# gatorstepper.net
KiCad netlist of a schematic drawn in EAGLE
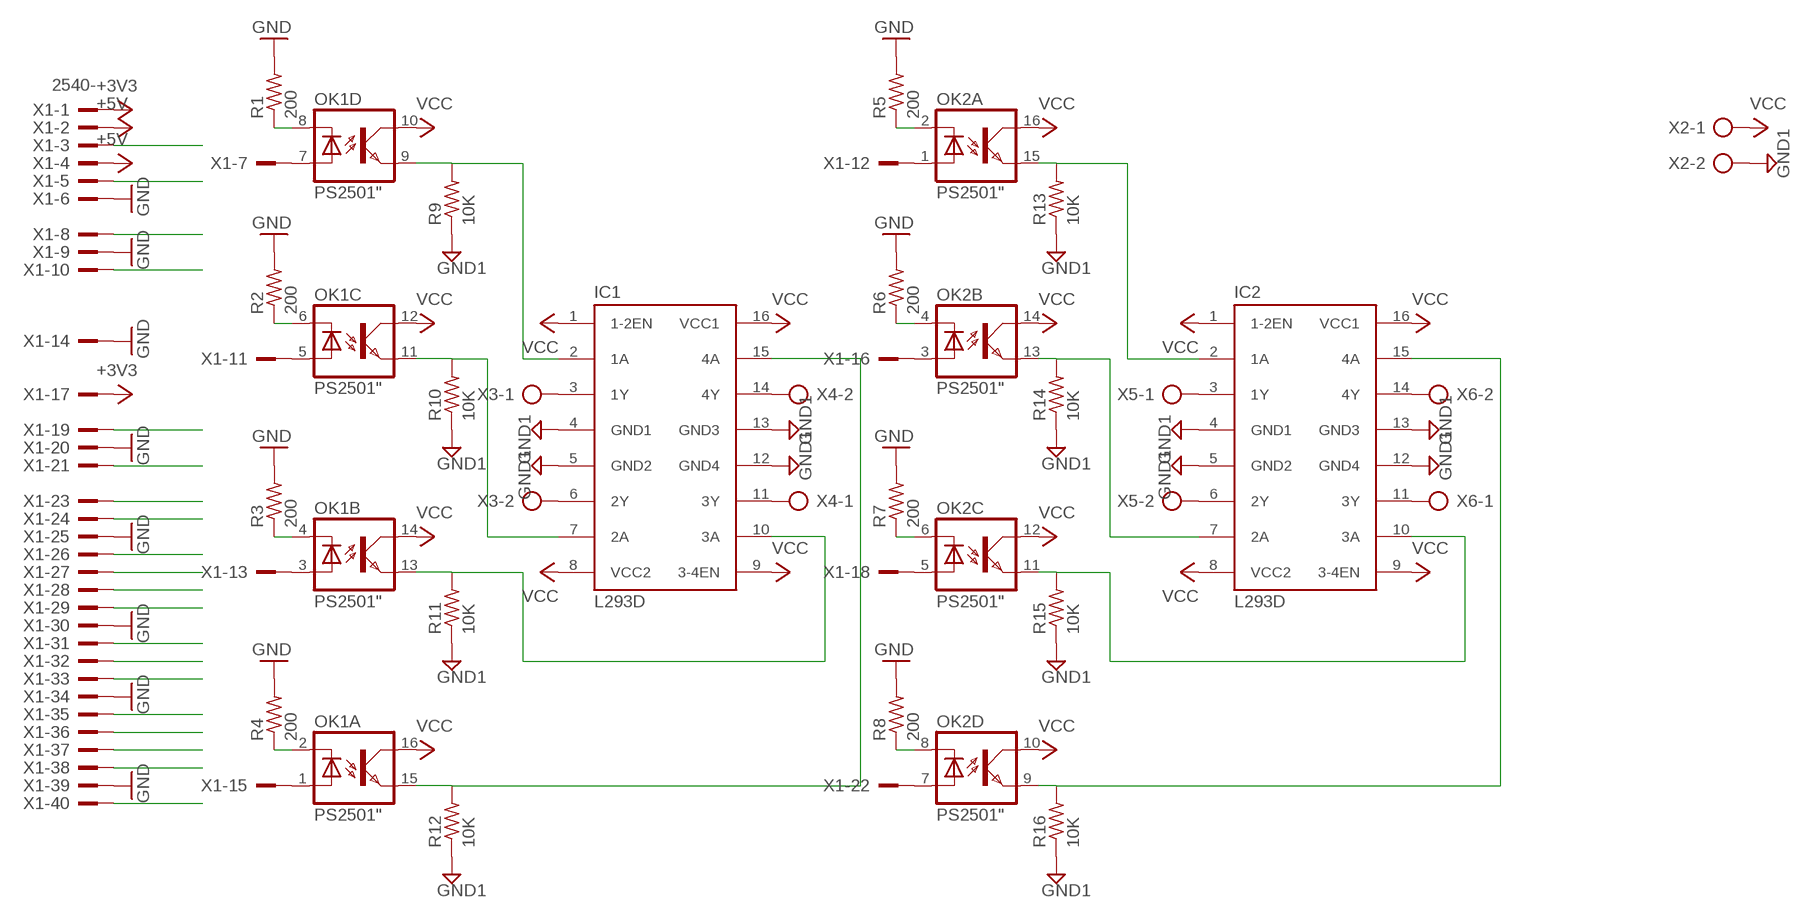
[diagram p0: schematic, sheet 1]

(export (version "E")
  (design (tool "Eeschema 10.0.6"))
  (components
    (comp (ref "IC1")
      (value "L293D")
      (footprint "eagle-import:DIL16")
      (libsource (lib "eagle-import") (part "L293D"))
    )
    (comp (ref "IC2")
      (value "L293D")
      (footprint "eagle-import:DIL16")
      (libsource (lib "eagle-import") (part "L293D"))
    )
    (comp (ref "OK1")
      (value "PS2501\"")
      (footprint "eagle-import:DIL16")
      (libsource (lib "eagle-import") (part "PS2501{dblquote}"))
    )
    (comp (ref "OK2")
      (value "PS2501\"")
      (footprint "eagle-import:DIL16")
      (libsource (lib "eagle-import") (part "PS2501{dblquote}"))
    )
    (comp (ref "R1")
      (value "200")
      (footprint "eagle-import:0207_12")
      (libsource (lib "eagle-import") (part "R-US_0207/12"))
    )
    (comp (ref "R2")
      (value "200")
      (footprint "eagle-import:0207_12")
      (libsource (lib "eagle-import") (part "R-US_0207/12"))
    )
    (comp (ref "R3")
      (value "200")
      (footprint "eagle-import:0207_12")
      (libsource (lib "eagle-import") (part "R-US_0207/12"))
    )
    (comp (ref "R4")
      (value "200")
      (footprint "eagle-import:0207_12")
      (libsource (lib "eagle-import") (part "R-US_0207/12"))
    )
    (comp (ref "R5")
      (value "200")
      (footprint "eagle-import:0207_12")
      (libsource (lib "eagle-import") (part "R-US_0207/12"))
    )
    (comp (ref "R6")
      (value "200")
      (footprint "eagle-import:0207_12")
      (libsource (lib "eagle-import") (part "R-US_0207/12"))
    )
    (comp (ref "R7")
      (value "200")
      (footprint "eagle-import:0207_12")
      (libsource (lib "eagle-import") (part "R-US_0207/12"))
    )
    (comp (ref "R8")
      (value "200")
      (footprint "eagle-import:0207_12")
      (libsource (lib "eagle-import") (part "R-US_0207/12"))
    )
    (comp (ref "R9")
      (value "10K")
      (footprint "eagle-import:0207_12")
      (libsource (lib "eagle-import") (part "R-US_0207/12"))
    )
    (comp (ref "R10")
      (value "10K")
      (footprint "eagle-import:0207_12")
      (libsource (lib "eagle-import") (part "R-US_0207/12"))
    )
    (comp (ref "R11")
      (value "10K")
      (footprint "eagle-import:0207_12")
      (libsource (lib "eagle-import") (part "R-US_0207/12"))
    )
    (comp (ref "R12")
      (value "10K")
      (footprint "eagle-import:0207_12")
      (libsource (lib "eagle-import") (part "R-US_0207/12"))
    )
    (comp (ref "R13")
      (value "10K")
      (footprint "eagle-import:0207_12")
      (libsource (lib "eagle-import") (part "R-US_0207/12"))
    )
    (comp (ref "R14")
      (value "10K")
      (footprint "eagle-import:0207_12")
      (libsource (lib "eagle-import") (part "R-US_0207/12"))
    )
    (comp (ref "R15")
      (value "10K")
      (footprint "eagle-import:0207_12")
      (libsource (lib "eagle-import") (part "R-US_0207/12"))
    )
    (comp (ref "R16")
      (value "10K")
      (footprint "eagle-import:0207_12")
      (libsource (lib "eagle-import") (part "R-US_0207/12"))
    )
    (comp (ref "X1")
      (value "2540-")
      (footprint "eagle-import:PAK100_2500-40")
      (libsource (lib "eagle-import") (part "2540-"))
    )
    (comp (ref "X2")
      (value "AK300/2")
      (footprint "eagle-import:AK300_2")
      (libsource (lib "eagle-import") (part "AK300/2"))
    )
    (comp (ref "X3")
      (value "AK300/2")
      (footprint "eagle-import:AK300_2")
      (libsource (lib "eagle-import") (part "AK300/2"))
    )
    (comp (ref "X4")
      (value "AK300/2")
      (footprint "eagle-import:AK300_2")
      (libsource (lib "eagle-import") (part "AK300/2"))
    )
    (comp (ref "X5")
      (value "AK300/2")
      (footprint "eagle-import:AK300_2")
      (libsource (lib "eagle-import") (part "AK300/2"))
    )
    (comp (ref "X6")
      (value "AK300/2")
      (footprint "eagle-import:AK300_2")
      (libsource (lib "eagle-import") (part "AK300/2"))
    )
  )
  (nets
    (net (code "1") (name "+3V3") (class "Default")
      (node (ref "X1") (pin "1") (pinfunction "KL_1") (pintype "passive"))
      (node (ref "X1") (pin "17") (pinfunction "KL_17") (pintype "passive"))
    )
    (net (code "2") (name "+5V") (class "Default")
      (node (ref "X1") (pin "2") (pinfunction "KL_2") (pintype "passive"))
      (node (ref "X1") (pin "4") (pinfunction "KL_4") (pintype "passive"))
    )
    (net (code "3") (name "GND") (class "Default")
      (node (ref "R1") (pin "2") (pinfunction "2_2") (pintype "passive"))
      (node (ref "R2") (pin "2") (pinfunction "2_2") (pintype "passive"))
      (node (ref "R3") (pin "2") (pinfunction "2_2") (pintype "passive"))
      (node (ref "R4") (pin "2") (pinfunction "2_2") (pintype "passive"))
      (node (ref "R5") (pin "2") (pinfunction "2_2") (pintype "passive"))
      (node (ref "R6") (pin "2") (pinfunction "2_2") (pintype "passive"))
      (node (ref "R7") (pin "2") (pinfunction "2_2") (pintype "passive"))
      (node (ref "R8") (pin "2") (pinfunction "2_2") (pintype "passive"))
      (node (ref "X1") (pin "14") (pinfunction "KL_14") (pintype "passive"))
      (node (ref "X1") (pin "20") (pinfunction "KL_20") (pintype "passive"))
      (node (ref "X1") (pin "25") (pinfunction "KL_25") (pintype "passive"))
      (node (ref "X1") (pin "30") (pinfunction "KL_30") (pintype "passive"))
      (node (ref "X1") (pin "34") (pinfunction "KL_34") (pintype "passive"))
      (node (ref "X1") (pin "39") (pinfunction "KL_39") (pintype "passive"))
      (node (ref "X1") (pin "6") (pinfunction "KL_6") (pintype "passive"))
      (node (ref "X1") (pin "9") (pinfunction "KL_9") (pintype "passive"))
    )
    (net (code "4") (name "GND1") (class "Default")
      (node (ref "IC1") (pin "12") (pinfunction "GND4_12") (pintype "power_in"))
      (node (ref "IC1") (pin "13") (pinfunction "GND3_13") (pintype "power_in"))
      (node (ref "IC1") (pin "4") (pinfunction "GND1_4") (pintype "power_in"))
      (node (ref "IC1") (pin "5") (pinfunction "GND2_5") (pintype "power_in"))
      (node (ref "IC2") (pin "12") (pinfunction "GND4_12") (pintype "power_in"))
      (node (ref "IC2") (pin "13") (pinfunction "GND3_13") (pintype "power_in"))
      (node (ref "IC2") (pin "4") (pinfunction "GND1_4") (pintype "power_in"))
      (node (ref "IC2") (pin "5") (pinfunction "GND2_5") (pintype "power_in"))
      (node (ref "R10") (pin "1") (pinfunction "1_1") (pintype "passive"))
      (node (ref "R11") (pin "1") (pinfunction "1_1") (pintype "passive"))
      (node (ref "R12") (pin "1") (pinfunction "1_1") (pintype "passive"))
      (node (ref "R13") (pin "1") (pinfunction "1_1") (pintype "passive"))
      (node (ref "R14") (pin "1") (pinfunction "1_1") (pintype "passive"))
      (node (ref "R15") (pin "1") (pinfunction "1_1") (pintype "passive"))
      (node (ref "R16") (pin "1") (pinfunction "1_1") (pintype "passive"))
      (node (ref "R9") (pin "1") (pinfunction "1_1") (pintype "passive"))
      (node (ref "X2") (pin "2") (pinfunction "KL_2") (pintype "passive"))
    )
    (net (code "5") (name "Net-(IC1-1A)") (class "Default")
      (node (ref "IC1") (pin "2") (pinfunction "1A_2") (pintype "input"))
      (node (ref "OK1") (pin "9") (pinfunction "EMI_9") (pintype "passive"))
      (node (ref "R9") (pin "2") (pinfunction "2_2") (pintype "passive"))
    )
    (net (code "6") (name "Net-(IC1-1Y)") (class "Default")
      (node (ref "IC1") (pin "3") (pinfunction "1Y_3") (pintype "output"))
      (node (ref "X3") (pin "1") (pinfunction "KL_1") (pintype "passive"))
    )
    (net (code "7") (name "Net-(IC1-2A)") (class "Default")
      (node (ref "IC1") (pin "7") (pinfunction "2A_7") (pintype "input"))
      (node (ref "OK1") (pin "11") (pinfunction "EMI_11") (pintype "passive"))
      (node (ref "R10") (pin "2") (pinfunction "2_2") (pintype "passive"))
    )
    (net (code "8") (name "Net-(IC1-2Y)") (class "Default")
      (node (ref "IC1") (pin "6") (pinfunction "2Y_6") (pintype "output"))
      (node (ref "X3") (pin "2") (pinfunction "KL_2") (pintype "passive"))
    )
    (net (code "9") (name "Net-(IC1-3A)") (class "Default")
      (node (ref "IC1") (pin "10") (pinfunction "3A_10") (pintype "input"))
      (node (ref "OK1") (pin "13") (pinfunction "EMI_13") (pintype "passive"))
      (node (ref "R11") (pin "2") (pinfunction "2_2") (pintype "passive"))
    )
    (net (code "10") (name "Net-(IC1-3Y)") (class "Default")
      (node (ref "IC1") (pin "11") (pinfunction "3Y_11") (pintype "output"))
      (node (ref "X4") (pin "1") (pinfunction "KL_1") (pintype "passive"))
    )
    (net (code "11") (name "Net-(IC1-4A)") (class "Default")
      (node (ref "IC1") (pin "15") (pinfunction "4A_15") (pintype "input"))
      (node (ref "OK1") (pin "15") (pinfunction "EMI_15") (pintype "passive"))
      (node (ref "R12") (pin "2") (pinfunction "2_2") (pintype "passive"))
    )
    (net (code "12") (name "Net-(IC1-4Y)") (class "Default")
      (node (ref "IC1") (pin "14") (pinfunction "4Y_14") (pintype "output"))
      (node (ref "X4") (pin "2") (pinfunction "KL_2") (pintype "passive"))
    )
    (net (code "13") (name "Net-(IC2-1A)") (class "Default")
      (node (ref "IC2") (pin "2") (pinfunction "1A_2") (pintype "input"))
      (node (ref "OK2") (pin "15") (pinfunction "EMI_15") (pintype "passive"))
      (node (ref "R13") (pin "2") (pinfunction "2_2") (pintype "passive"))
    )
    (net (code "14") (name "Net-(IC2-1Y)") (class "Default")
      (node (ref "IC2") (pin "3") (pinfunction "1Y_3") (pintype "output"))
      (node (ref "X5") (pin "1") (pinfunction "KL_1") (pintype "passive"))
    )
    (net (code "15") (name "Net-(IC2-2A)") (class "Default")
      (node (ref "IC2") (pin "7") (pinfunction "2A_7") (pintype "input"))
      (node (ref "OK2") (pin "13") (pinfunction "EMI_13") (pintype "passive"))
      (node (ref "R14") (pin "2") (pinfunction "2_2") (pintype "passive"))
    )
    (net (code "16") (name "Net-(IC2-2Y)") (class "Default")
      (node (ref "IC2") (pin "6") (pinfunction "2Y_6") (pintype "output"))
      (node (ref "X5") (pin "2") (pinfunction "KL_2") (pintype "passive"))
    )
    (net (code "17") (name "Net-(IC2-3A)") (class "Default")
      (node (ref "IC2") (pin "10") (pinfunction "3A_10") (pintype "input"))
      (node (ref "OK2") (pin "11") (pinfunction "EMI_11") (pintype "passive"))
      (node (ref "R15") (pin "2") (pinfunction "2_2") (pintype "passive"))
    )
    (net (code "18") (name "Net-(IC2-3Y)") (class "Default")
      (node (ref "IC2") (pin "11") (pinfunction "3Y_11") (pintype "output"))
      (node (ref "X6") (pin "1") (pinfunction "KL_1") (pintype "passive"))
    )
    (net (code "19") (name "Net-(IC2-4A)") (class "Default")
      (node (ref "IC2") (pin "15") (pinfunction "4A_15") (pintype "input"))
      (node (ref "OK2") (pin "9") (pinfunction "EMI_9") (pintype "passive"))
      (node (ref "R16") (pin "2") (pinfunction "2_2") (pintype "passive"))
    )
    (net (code "20") (name "Net-(IC2-4Y)") (class "Default")
      (node (ref "IC2") (pin "14") (pinfunction "4Y_14") (pintype "output"))
      (node (ref "X6") (pin "2") (pinfunction "KL_2") (pintype "passive"))
    )
    (net (code "21") (name "Net-(OK1A-A)") (class "Default")
      (node (ref "OK1") (pin "1") (pinfunction "A_1") (pintype "passive"))
      (node (ref "X1") (pin "15") (pinfunction "KL_15") (pintype "passive"))
    )
    (net (code "22") (name "Net-(OK1A-C)") (class "Default")
      (node (ref "OK1") (pin "2") (pinfunction "C_2") (pintype "passive"))
      (node (ref "R4") (pin "1") (pinfunction "1_1") (pintype "passive"))
    )
    (net (code "23") (name "Net-(OK1B-A)") (class "Default")
      (node (ref "OK1") (pin "3") (pinfunction "A_3") (pintype "passive"))
      (node (ref "X1") (pin "13") (pinfunction "KL_13") (pintype "passive"))
    )
    (net (code "24") (name "Net-(OK1B-C)") (class "Default")
      (node (ref "OK1") (pin "4") (pinfunction "C_4") (pintype "passive"))
      (node (ref "R3") (pin "1") (pinfunction "1_1") (pintype "passive"))
    )
    (net (code "25") (name "Net-(OK1C-A)") (class "Default")
      (node (ref "OK1") (pin "5") (pinfunction "A_5") (pintype "passive"))
      (node (ref "X1") (pin "11") (pinfunction "KL_11") (pintype "passive"))
    )
    (net (code "26") (name "Net-(OK1C-C)") (class "Default")
      (node (ref "OK1") (pin "6") (pinfunction "C_6") (pintype "passive"))
      (node (ref "R2") (pin "1") (pinfunction "1_1") (pintype "passive"))
    )
    (net (code "27") (name "Net-(OK1D-A)") (class "Default")
      (node (ref "OK1") (pin "7") (pinfunction "A_7") (pintype "passive"))
      (node (ref "X1") (pin "7") (pinfunction "KL_7") (pintype "passive"))
    )
    (net (code "28") (name "Net-(OK1D-C)") (class "Default")
      (node (ref "OK1") (pin "8") (pinfunction "C_8") (pintype "passive"))
      (node (ref "R1") (pin "1") (pinfunction "1_1") (pintype "passive"))
    )
    (net (code "29") (name "Net-(OK2A-A)") (class "Default")
      (node (ref "OK2") (pin "1") (pinfunction "A_1") (pintype "passive"))
      (node (ref "X1") (pin "12") (pinfunction "KL_12") (pintype "passive"))
    )
    (net (code "30") (name "Net-(OK2A-C)") (class "Default")
      (node (ref "OK2") (pin "2") (pinfunction "C_2") (pintype "passive"))
      (node (ref "R5") (pin "1") (pinfunction "1_1") (pintype "passive"))
    )
    (net (code "31") (name "Net-(OK2B-A)") (class "Default")
      (node (ref "OK2") (pin "3") (pinfunction "A_3") (pintype "passive"))
      (node (ref "X1") (pin "16") (pinfunction "KL_16") (pintype "passive"))
    )
    (net (code "32") (name "Net-(OK2B-C)") (class "Default")
      (node (ref "OK2") (pin "4") (pinfunction "C_4") (pintype "passive"))
      (node (ref "R6") (pin "1") (pinfunction "1_1") (pintype "passive"))
    )
    (net (code "33") (name "Net-(OK2C-A)") (class "Default")
      (node (ref "OK2") (pin "5") (pinfunction "A_5") (pintype "passive"))
      (node (ref "X1") (pin "18") (pinfunction "KL_18") (pintype "passive"))
    )
    (net (code "34") (name "Net-(OK2C-C)") (class "Default")
      (node (ref "OK2") (pin "6") (pinfunction "C_6") (pintype "passive"))
      (node (ref "R7") (pin "1") (pinfunction "1_1") (pintype "passive"))
    )
    (net (code "35") (name "Net-(OK2D-A)") (class "Default")
      (node (ref "OK2") (pin "7") (pinfunction "A_7") (pintype "passive"))
      (node (ref "X1") (pin "22") (pinfunction "KL_22") (pintype "passive"))
    )
    (net (code "36") (name "Net-(OK2D-C)") (class "Default")
      (node (ref "OK2") (pin "8") (pinfunction "C_8") (pintype "passive"))
      (node (ref "R8") (pin "1") (pinfunction "1_1") (pintype "passive"))
    )
    (net (code "37") (name "VCC") (class "Default")
      (node (ref "IC1") (pin "1") (pinfunction "1-2EN_1") (pintype "input"))
      (node (ref "IC1") (pin "16") (pinfunction "VCC1_16") (pintype "power_in"))
      (node (ref "IC1") (pin "8") (pinfunction "VCC2_8") (pintype "power_in"))
      (node (ref "IC1") (pin "9") (pinfunction "3-4EN_9") (pintype "input"))
      (node (ref "IC2") (pin "1") (pinfunction "1-2EN_1") (pintype "input"))
      (node (ref "IC2") (pin "16") (pinfunction "VCC1_16") (pintype "power_in"))
      (node (ref "IC2") (pin "8") (pinfunction "VCC2_8") (pintype "power_in"))
      (node (ref "IC2") (pin "9") (pinfunction "3-4EN_9") (pintype "input"))
      (node (ref "OK1") (pin "10") (pinfunction "COL_10") (pintype "passive"))
      (node (ref "OK1") (pin "12") (pinfunction "COL_12") (pintype "passive"))
      (node (ref "OK1") (pin "14") (pinfunction "COL_14") (pintype "passive"))
      (node (ref "OK1") (pin "16") (pinfunction "COL_16") (pintype "passive"))
      (node (ref "OK2") (pin "10") (pinfunction "COL_10") (pintype "passive"))
      (node (ref "OK2") (pin "12") (pinfunction "COL_12") (pintype "passive"))
      (node (ref "OK2") (pin "14") (pinfunction "COL_14") (pintype "passive"))
      (node (ref "OK2") (pin "16") (pinfunction "COL_16") (pintype "passive"))
      (node (ref "X2") (pin "1") (pinfunction "KL_1") (pintype "passive"))
    )
    (net (code "38") (name "unconnected-(X1AA-KL-Pad33)") (class "Default")
      (node (ref "X1") (pin "33") (pinfunction "KL_33") (pintype "passive"))
    )
    (net (code "39") (name "unconnected-(X1AC-KL-Pad35)") (class "Default")
      (node (ref "X1") (pin "35") (pinfunction "KL_35") (pintype "passive"))
    )
    (net (code "40") (name "unconnected-(X1AD-KL-Pad36)") (class "Default")
      (node (ref "X1") (pin "36") (pinfunction "KL_36") (pintype "passive"))
    )
    (net (code "41") (name "unconnected-(X1AE-KL-Pad37)") (class "Default")
      (node (ref "X1") (pin "37") (pinfunction "KL_37") (pintype "passive"))
    )
    (net (code "42") (name "unconnected-(X1AF-KL-Pad38)") (class "Default")
      (node (ref "X1") (pin "38") (pinfunction "KL_38") (pintype "passive"))
    )
    (net (code "43") (name "unconnected-(X1AI-KL-Pad40)") (class "Default")
      (node (ref "X1") (pin "40") (pinfunction "KL_40") (pintype "passive"))
    )
    (net (code "44") (name "unconnected-(X1AJ-KL-Pad5)") (class "Default")
      (node (ref "X1") (pin "5") (pinfunction "KL_5") (pintype "passive"))
    )
    (net (code "45") (name "unconnected-(X1AM-KL-Pad8)") (class "Default")
      (node (ref "X1") (pin "8") (pinfunction "KL_8") (pintype "passive"))
    )
    (net (code "46") (name "unconnected-(X1B-KL-Pad10)") (class "Default")
      (node (ref "X1") (pin "10") (pinfunction "KL_10") (pintype "passive"))
    )
    (net (code "47") (name "unconnected-(X1K-KL-Pad19)") (class "Default")
      (node (ref "X1") (pin "19") (pinfunction "KL_19") (pintype "passive"))
    )
    (net (code "48") (name "unconnected-(X1N-KL-Pad21)") (class "Default")
      (node (ref "X1") (pin "21") (pinfunction "KL_21") (pintype "passive"))
    )
    (net (code "49") (name "unconnected-(X1P-KL-Pad23)") (class "Default")
      (node (ref "X1") (pin "23") (pinfunction "KL_23") (pintype "passive"))
    )
    (net (code "50") (name "unconnected-(X1Q-KL-Pad24)") (class "Default")
      (node (ref "X1") (pin "24") (pinfunction "KL_24") (pintype "passive"))
    )
    (net (code "51") (name "unconnected-(X1S-KL-Pad26)") (class "Default")
      (node (ref "X1") (pin "26") (pinfunction "KL_26") (pintype "passive"))
    )
    (net (code "52") (name "unconnected-(X1T-KL-Pad27)") (class "Default")
      (node (ref "X1") (pin "27") (pinfunction "KL_27") (pintype "passive"))
    )
    (net (code "53") (name "unconnected-(X1U-KL-Pad28)") (class "Default")
      (node (ref "X1") (pin "28") (pinfunction "KL_28") (pintype "passive"))
    )
    (net (code "54") (name "unconnected-(X1V-KL-Pad29)") (class "Default")
      (node (ref "X1") (pin "29") (pinfunction "KL_29") (pintype "passive"))
    )
    (net (code "55") (name "unconnected-(X1W-KL-Pad3)") (class "Default")
      (node (ref "X1") (pin "3") (pinfunction "KL_3") (pintype "passive"))
    )
    (net (code "56") (name "unconnected-(X1Y-KL-Pad31)") (class "Default")
      (node (ref "X1") (pin "31") (pinfunction "KL_31") (pintype "passive"))
    )
    (net (code "57") (name "unconnected-(X1Z-KL-Pad32)") (class "Default")
      (node (ref "X1") (pin "32") (pinfunction "KL_32") (pintype "passive"))
    )
  )
)
